# artProject_X.net
KiCad netlist of a schematic drawn in EAGLE
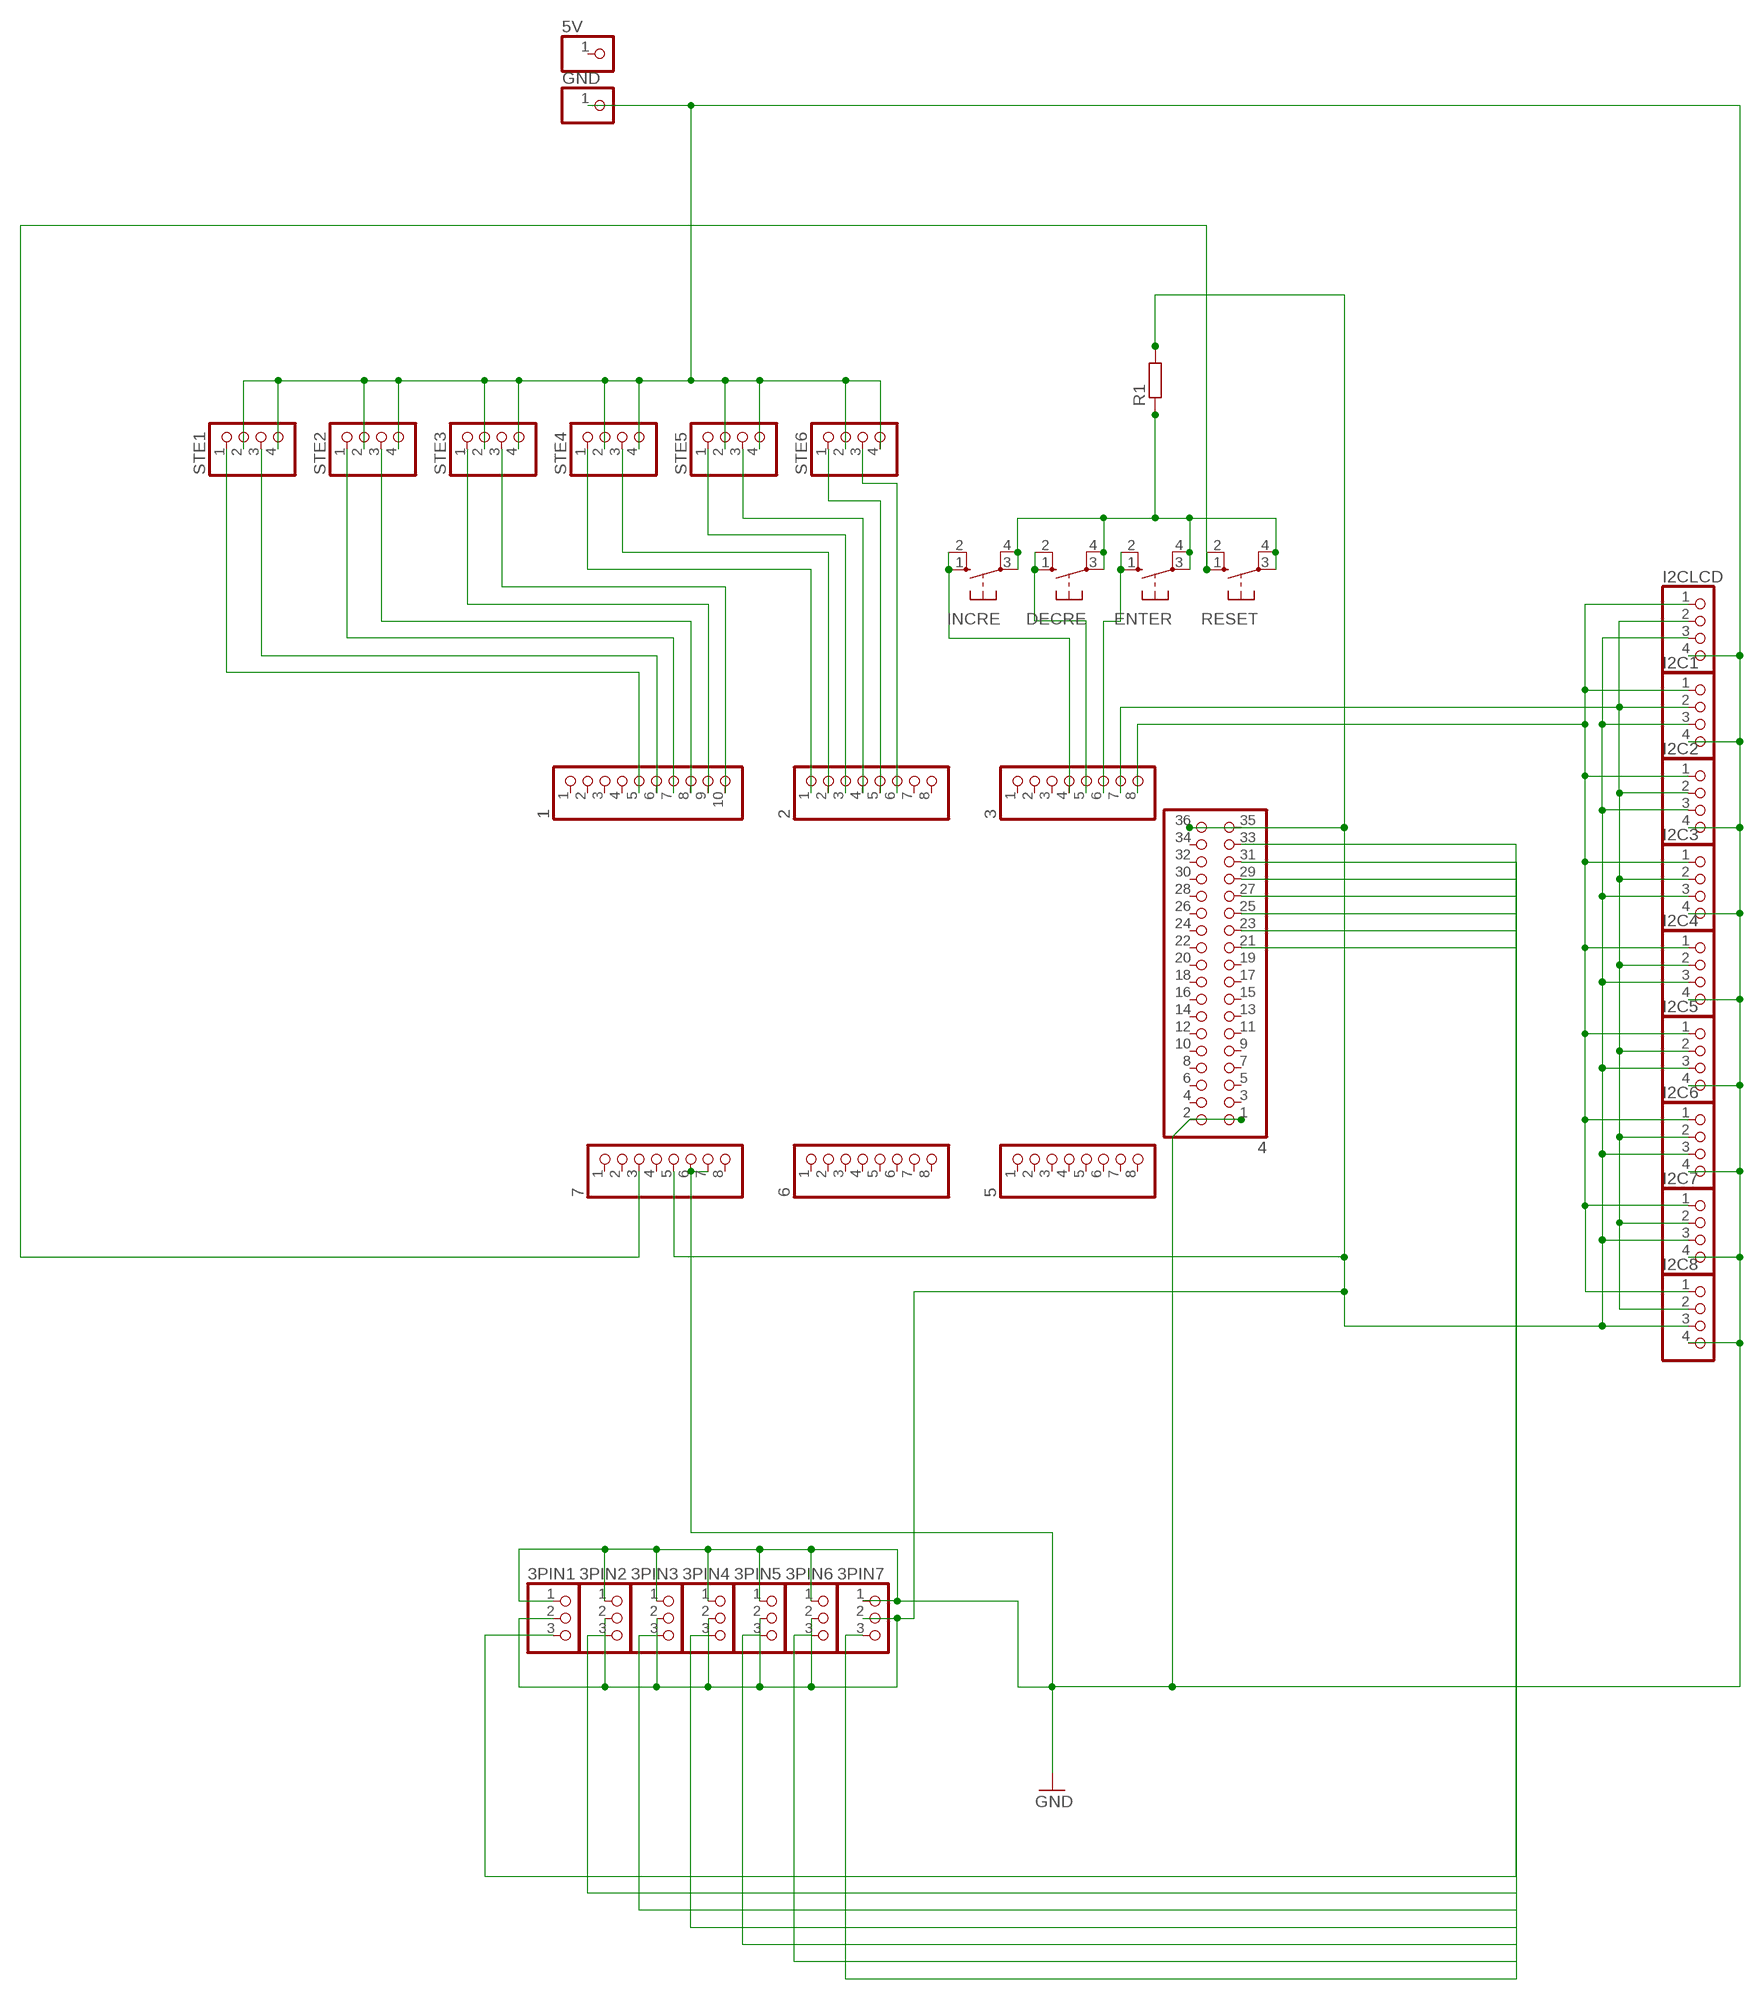
[diagram p0: schematic, sheet 1]

(export (version "E")
  (design (tool "Eeschema 10.0.6"))
  (components
    (comp (ref "1")
      (value "PINHD-1X10")
      (footprint "eagle-import:1X10")
      (libsource (lib "eagle-import") (part "PINHD-1X10"))
    )
    (comp (ref "2")
      (value "PINHD-1X8")
      (footprint "eagle-import:1X08")
      (libsource (lib "eagle-import") (part "PINHD-1X8"))
    )
    (comp (ref "3")
      (value "PINHD-1X8")
      (footprint "eagle-import:1X08")
      (libsource (lib "eagle-import") (part "PINHD-1X8"))
    )
    (comp (ref "3PIN1")
      (value "PINHD-1X3")
      (footprint "eagle-import:1X03")
      (libsource (lib "eagle-import") (part "PINHD-1X3"))
    )
    (comp (ref "3PIN2")
      (value "PINHD-1X3")
      (footprint "eagle-import:1X03")
      (libsource (lib "eagle-import") (part "PINHD-1X3"))
    )
    (comp (ref "3PIN3")
      (value "PINHD-1X3")
      (footprint "eagle-import:1X03")
      (libsource (lib "eagle-import") (part "PINHD-1X3"))
    )
    (comp (ref "3PIN4")
      (value "PINHD-1X3")
      (footprint "eagle-import:1X03")
      (libsource (lib "eagle-import") (part "PINHD-1X3"))
    )
    (comp (ref "3PIN5")
      (value "PINHD-1X3")
      (footprint "eagle-import:1X03")
      (libsource (lib "eagle-import") (part "PINHD-1X3"))
    )
    (comp (ref "3PIN6")
      (value "PINHD-1X3")
      (footprint "eagle-import:1X03")
      (libsource (lib "eagle-import") (part "PINHD-1X3"))
    )
    (comp (ref "3PIN7")
      (value "PINHD-1X3")
      (footprint "eagle-import:1X03")
      (libsource (lib "eagle-import") (part "PINHD-1X3"))
    )
    (comp (ref "4")
      (value "PINHD-2X18")
      (footprint "eagle-import:2X18")
      (libsource (lib "eagle-import") (part "PINHD-2X18"))
    )
    (comp (ref "5")
      (value "PINHD-1X8")
      (footprint "eagle-import:1X08")
      (libsource (lib "eagle-import") (part "PINHD-1X8"))
    )
    (comp (ref "5V")
      (value "PINHD-1X1")
      (footprint "eagle-import:1X01")
      (libsource (lib "eagle-import") (part "PINHD-1X1"))
    )
    (comp (ref "6")
      (value "PINHD-1X8")
      (footprint "eagle-import:1X08")
      (libsource (lib "eagle-import") (part "PINHD-1X8"))
    )
    (comp (ref "7")
      (value "PINHD-1X8")
      (footprint "eagle-import:1X08")
      (libsource (lib "eagle-import") (part "PINHD-1X8"))
    )
    (comp (ref "DECRE")
      (value "10-XX")
      (footprint "eagle-import:B3F-10XX")
      (fields (field (name "MPN") "B3F-1000"))
      (libsource (lib "eagle-import") (part "10-XX"))
    )
    (comp (ref "ENTER")
      (value "10-XX")
      (footprint "eagle-import:B3F-10XX")
      (fields (field (name "MPN") "B3F-1000"))
      (libsource (lib "eagle-import") (part "10-XX"))
    )
    (comp (ref "GND")
      (value "PINHD-1X1")
      (footprint "eagle-import:1X01")
      (libsource (lib "eagle-import") (part "PINHD-1X1"))
    )
    (comp (ref "I2C1")
      (value "PINHD-1X4")
      (footprint "eagle-import:1X04")
      (libsource (lib "eagle-import") (part "PINHD-1X4"))
    )
    (comp (ref "I2C2")
      (value "PINHD-1X4")
      (footprint "eagle-import:1X04")
      (libsource (lib "eagle-import") (part "PINHD-1X4"))
    )
    (comp (ref "I2C3")
      (value "PINHD-1X4")
      (footprint "eagle-import:1X04")
      (libsource (lib "eagle-import") (part "PINHD-1X4"))
    )
    (comp (ref "I2C4")
      (value "PINHD-1X4")
      (footprint "eagle-import:1X04")
      (libsource (lib "eagle-import") (part "PINHD-1X4"))
    )
    (comp (ref "I2C5")
      (value "PINHD-1X4")
      (footprint "eagle-import:1X04")
      (libsource (lib "eagle-import") (part "PINHD-1X4"))
    )
    (comp (ref "I2C6")
      (value "PINHD-1X4")
      (footprint "eagle-import:1X04")
      (libsource (lib "eagle-import") (part "PINHD-1X4"))
    )
    (comp (ref "I2C7")
      (value "PINHD-1X4")
      (footprint "eagle-import:1X04")
      (libsource (lib "eagle-import") (part "PINHD-1X4"))
    )
    (comp (ref "I2C8")
      (value "PINHD-1X4")
      (footprint "eagle-import:1X04")
      (libsource (lib "eagle-import") (part "PINHD-1X4"))
    )
    (comp (ref "I2CLCD")
      (value "PINHD-1X4")
      (footprint "eagle-import:1X04")
      (libsource (lib "eagle-import") (part "PINHD-1X4"))
    )
    (comp (ref "INCRE")
      (value "10-XX")
      (footprint "eagle-import:B3F-10XX")
      (fields (field (name "MPN") "B3F-1000"))
      (libsource (lib "eagle-import") (part "10-XX"))
    )
    (comp (ref "R1")
      (value "R-EU_0204/7")
      (footprint "eagle-import:0204_7")
      (libsource (lib "eagle-import") (part "R-EU_0204/7"))
    )
    (comp (ref "RESET")
      (value "10-XX")
      (footprint "eagle-import:B3F-10XX")
      (fields (field (name "MPN") "B3F-1000"))
      (libsource (lib "eagle-import") (part "10-XX"))
    )
    (comp (ref "STE1")
      (value "PINHD-1X4")
      (footprint "eagle-import:1X04")
      (libsource (lib "eagle-import") (part "PINHD-1X4"))
    )
    (comp (ref "STE2")
      (value "PINHD-1X4")
      (footprint "eagle-import:1X04")
      (libsource (lib "eagle-import") (part "PINHD-1X4"))
    )
    (comp (ref "STE3")
      (value "PINHD-1X4")
      (footprint "eagle-import:1X04")
      (libsource (lib "eagle-import") (part "PINHD-1X4"))
    )
    (comp (ref "STE4")
      (value "PINHD-1X4")
      (footprint "eagle-import:1X04")
      (libsource (lib "eagle-import") (part "PINHD-1X4"))
    )
    (comp (ref "STE5")
      (value "PINHD-1X4")
      (footprint "eagle-import:1X04")
      (libsource (lib "eagle-import") (part "PINHD-1X4"))
    )
    (comp (ref "STE6")
      (value "PINHD-1X4")
      (footprint "eagle-import:1X04")
      (libsource (lib "eagle-import") (part "PINHD-1X4"))
    )
  )
  (nets
    (net (code "1") (name "GND") (class "Default")
      (node (ref "3PIN1") (pin "1") (pinfunction "1_1") (pintype "passive"))
      (node (ref "3PIN2") (pin "1") (pinfunction "1_1") (pintype "passive"))
      (node (ref "3PIN3") (pin "1") (pinfunction "1_1") (pintype "passive"))
      (node (ref "3PIN4") (pin "1") (pinfunction "1_1") (pintype "passive"))
      (node (ref "3PIN5") (pin "1") (pinfunction "1_1") (pintype "passive"))
      (node (ref "3PIN6") (pin "1") (pinfunction "1_1") (pintype "passive"))
      (node (ref "3PIN7") (pin "1") (pinfunction "1_1") (pintype "passive"))
      (node (ref "4") (pin "1") (pinfunction "1_1") (pintype "passive"))
      (node (ref "4") (pin "2") (pinfunction "2_2") (pintype "passive"))
      (node (ref "7") (pin "6") (pinfunction "6_6") (pintype "passive"))
      (node (ref "7") (pin "7") (pinfunction "7_7") (pintype "passive"))
      (node (ref "GND") (pin "1") (pinfunction "1_1") (pintype "passive"))
      (node (ref "I2C1") (pin "4") (pinfunction "4_4") (pintype "passive"))
      (node (ref "I2C2") (pin "4") (pinfunction "4_4") (pintype "passive"))
      (node (ref "I2C3") (pin "4") (pinfunction "4_4") (pintype "passive"))
      (node (ref "I2C4") (pin "4") (pinfunction "4_4") (pintype "passive"))
      (node (ref "I2C5") (pin "4") (pinfunction "4_4") (pintype "passive"))
      (node (ref "I2C6") (pin "4") (pinfunction "4_4") (pintype "passive"))
      (node (ref "I2C7") (pin "4") (pinfunction "4_4") (pintype "passive"))
      (node (ref "I2C8") (pin "4") (pinfunction "4_4") (pintype "passive"))
      (node (ref "I2CLCD") (pin "4") (pinfunction "4_4") (pintype "passive"))
      (node (ref "STE1") (pin "2") (pinfunction "2_2") (pintype "passive"))
      (node (ref "STE1") (pin "4") (pinfunction "4_4") (pintype "passive"))
      (node (ref "STE2") (pin "2") (pinfunction "2_2") (pintype "passive"))
      (node (ref "STE2") (pin "4") (pinfunction "4_4") (pintype "passive"))
      (node (ref "STE3") (pin "2") (pinfunction "2_2") (pintype "passive"))
      (node (ref "STE3") (pin "4") (pinfunction "4_4") (pintype "passive"))
      (node (ref "STE4") (pin "2") (pinfunction "2_2") (pintype "passive"))
      (node (ref "STE4") (pin "4") (pinfunction "4_4") (pintype "passive"))
      (node (ref "STE5") (pin "2") (pinfunction "2_2") (pintype "passive"))
      (node (ref "STE5") (pin "4") (pinfunction "4_4") (pintype "passive"))
      (node (ref "STE6") (pin "2") (pinfunction "2_2") (pintype "passive"))
      (node (ref "STE6") (pin "4") (pinfunction "4_4") (pintype "passive"))
    )
    (net (code "2") (name "Net-(1-Pad5)") (class "Default")
      (node (ref "1") (pin "5") (pinfunction "5_5") (pintype "passive"))
      (node (ref "STE1") (pin "1") (pinfunction "1_1") (pintype "passive"))
    )
    (net (code "3") (name "Net-(1-Pad6)") (class "Default")
      (node (ref "1") (pin "6") (pinfunction "6_6") (pintype "passive"))
      (node (ref "STE1") (pin "3") (pinfunction "3_3") (pintype "passive"))
    )
    (net (code "4") (name "Net-(1-Pad7)") (class "Default")
      (node (ref "1") (pin "7") (pinfunction "7_7") (pintype "passive"))
      (node (ref "STE2") (pin "1") (pinfunction "1_1") (pintype "passive"))
    )
    (net (code "5") (name "Net-(1-Pad8)") (class "Default")
      (node (ref "1") (pin "8") (pinfunction "8_8") (pintype "passive"))
      (node (ref "STE2") (pin "3") (pinfunction "3_3") (pintype "passive"))
    )
    (net (code "6") (name "Net-(1-Pad9)") (class "Default")
      (node (ref "1") (pin "9") (pinfunction "9_9") (pintype "passive"))
      (node (ref "STE3") (pin "1") (pinfunction "1_1") (pintype "passive"))
    )
    (net (code "7") (name "Net-(1-Pad10)") (class "Default")
      (node (ref "1") (pin "10") (pinfunction "10_10") (pintype "passive"))
      (node (ref "STE3") (pin "3") (pinfunction "3_3") (pintype "passive"))
    )
    (net (code "8") (name "Net-(2-Pad1)") (class "Default")
      (node (ref "2") (pin "1") (pinfunction "1_1") (pintype "passive"))
      (node (ref "STE4") (pin "1") (pinfunction "1_1") (pintype "passive"))
    )
    (net (code "9") (name "Net-(2-Pad2)") (class "Default")
      (node (ref "2") (pin "2") (pinfunction "2_2") (pintype "passive"))
      (node (ref "STE4") (pin "3") (pinfunction "3_3") (pintype "passive"))
    )
    (net (code "10") (name "Net-(2-Pad3)") (class "Default")
      (node (ref "2") (pin "3") (pinfunction "3_3") (pintype "passive"))
      (node (ref "STE5") (pin "1") (pinfunction "1_1") (pintype "passive"))
    )
    (net (code "11") (name "Net-(2-Pad4)") (class "Default")
      (node (ref "2") (pin "4") (pinfunction "4_4") (pintype "passive"))
      (node (ref "STE5") (pin "3") (pinfunction "3_3") (pintype "passive"))
    )
    (net (code "12") (name "Net-(2-Pad5)") (class "Default")
      (node (ref "2") (pin "5") (pinfunction "5_5") (pintype "passive"))
      (node (ref "STE6") (pin "1") (pinfunction "1_1") (pintype "passive"))
    )
    (net (code "13") (name "Net-(2-Pad6)") (class "Default")
      (node (ref "2") (pin "6") (pinfunction "6_6") (pintype "passive"))
      (node (ref "STE6") (pin "3") (pinfunction "3_3") (pintype "passive"))
    )
    (net (code "14") (name "Net-(3-Pad7)") (class "Default")
      (node (ref "3") (pin "7") (pinfunction "7_7") (pintype "passive"))
      (node (ref "I2C1") (pin "2") (pinfunction "2_2") (pintype "passive"))
      (node (ref "I2C2") (pin "2") (pinfunction "2_2") (pintype "passive"))
      (node (ref "I2C3") (pin "2") (pinfunction "2_2") (pintype "passive"))
      (node (ref "I2C4") (pin "2") (pinfunction "2_2") (pintype "passive"))
      (node (ref "I2C5") (pin "2") (pinfunction "2_2") (pintype "passive"))
      (node (ref "I2C6") (pin "2") (pinfunction "2_2") (pintype "passive"))
      (node (ref "I2C7") (pin "2") (pinfunction "2_2") (pintype "passive"))
      (node (ref "I2C8") (pin "2") (pinfunction "2_2") (pintype "passive"))
      (node (ref "I2CLCD") (pin "2") (pinfunction "2_2") (pintype "passive"))
    )
    (net (code "15") (name "Net-(3-Pad8)") (class "Default")
      (node (ref "3") (pin "8") (pinfunction "8_8") (pintype "passive"))
      (node (ref "I2C1") (pin "1") (pinfunction "1_1") (pintype "passive"))
      (node (ref "I2C2") (pin "1") (pinfunction "1_1") (pintype "passive"))
      (node (ref "I2C3") (pin "1") (pinfunction "1_1") (pintype "passive"))
      (node (ref "I2C4") (pin "1") (pinfunction "1_1") (pintype "passive"))
      (node (ref "I2C5") (pin "1") (pinfunction "1_1") (pintype "passive"))
      (node (ref "I2C6") (pin "1") (pinfunction "1_1") (pintype "passive"))
      (node (ref "I2C7") (pin "1") (pinfunction "1_1") (pintype "passive"))
      (node (ref "I2C8") (pin "1") (pinfunction "1_1") (pintype "passive"))
      (node (ref "I2CLCD") (pin "1") (pinfunction "1_1") (pintype "passive"))
    )
    (net (code "16") (name "Net-(3PIN1-Pad2)") (class "Default")
      (node (ref "3PIN1") (pin "2") (pinfunction "2_2") (pintype "passive"))
      (node (ref "3PIN2") (pin "2") (pinfunction "2_2") (pintype "passive"))
      (node (ref "3PIN3") (pin "2") (pinfunction "2_2") (pintype "passive"))
      (node (ref "3PIN4") (pin "2") (pinfunction "2_2") (pintype "passive"))
      (node (ref "3PIN5") (pin "2") (pinfunction "2_2") (pintype "passive"))
      (node (ref "3PIN6") (pin "2") (pinfunction "2_2") (pintype "passive"))
      (node (ref "3PIN7") (pin "2") (pinfunction "2_2") (pintype "passive"))
      (node (ref "4") (pin "35") (pinfunction "35_35") (pintype "passive"))
      (node (ref "4") (pin "36") (pinfunction "36_36") (pintype "passive"))
      (node (ref "7") (pin "5") (pinfunction "5_5") (pintype "passive"))
      (node (ref "I2C1") (pin "3") (pinfunction "3_3") (pintype "passive"))
      (node (ref "I2C2") (pin "3") (pinfunction "3_3") (pintype "passive"))
      (node (ref "I2C3") (pin "3") (pinfunction "3_3") (pintype "passive"))
      (node (ref "I2C4") (pin "3") (pinfunction "3_3") (pintype "passive"))
      (node (ref "I2C5") (pin "3") (pinfunction "3_3") (pintype "passive"))
      (node (ref "I2C6") (pin "3") (pinfunction "3_3") (pintype "passive"))
      (node (ref "I2C7") (pin "3") (pinfunction "3_3") (pintype "passive"))
      (node (ref "I2C8") (pin "3") (pinfunction "3_3") (pintype "passive"))
      (node (ref "I2CLCD") (pin "3") (pinfunction "3_3") (pintype "passive"))
      (node (ref "R1") (pin "2") (pinfunction "2_2") (pintype "passive"))
    )
    (net (code "17") (name "Net-(3PIN1-Pad3)") (class "Default")
      (node (ref "3PIN1") (pin "3") (pinfunction "3_3") (pintype "passive"))
      (node (ref "4") (pin "33") (pinfunction "33_33") (pintype "passive"))
    )
    (net (code "18") (name "Net-(3PIN2-Pad3)") (class "Default")
      (node (ref "3PIN2") (pin "3") (pinfunction "3_3") (pintype "passive"))
      (node (ref "4") (pin "31") (pinfunction "31_31") (pintype "passive"))
    )
    (net (code "19") (name "Net-(3PIN3-Pad3)") (class "Default")
      (node (ref "3PIN3") (pin "3") (pinfunction "3_3") (pintype "passive"))
      (node (ref "4") (pin "29") (pinfunction "29_29") (pintype "passive"))
    )
    (net (code "20") (name "Net-(3PIN4-Pad3)") (class "Default")
      (node (ref "3PIN4") (pin "3") (pinfunction "3_3") (pintype "passive"))
      (node (ref "4") (pin "27") (pinfunction "27_27") (pintype "passive"))
    )
    (net (code "21") (name "Net-(3PIN5-Pad3)") (class "Default")
      (node (ref "3PIN5") (pin "3") (pinfunction "3_3") (pintype "passive"))
      (node (ref "4") (pin "25") (pinfunction "25_25") (pintype "passive"))
    )
    (net (code "22") (name "Net-(3PIN6-Pad3)") (class "Default")
      (node (ref "3PIN6") (pin "3") (pinfunction "3_3") (pintype "passive"))
      (node (ref "4") (pin "23") (pinfunction "23_23") (pintype "passive"))
    )
    (net (code "23") (name "Net-(3PIN7-Pad3)") (class "Default")
      (node (ref "3PIN7") (pin "3") (pinfunction "3_3") (pintype "passive"))
      (node (ref "4") (pin "21") (pinfunction "21_21") (pintype "passive"))
    )
    (net (code "24") (name "Net-(DECRE-P)") (class "Default")
      (node (ref "DECRE") (pin "3") (pinfunction "P_3") (pintype "passive"))
      (node (ref "DECRE") (pin "4") (pinfunction "P1_4") (pintype "passive"))
      (node (ref "ENTER") (pin "3") (pinfunction "P_3") (pintype "passive"))
      (node (ref "ENTER") (pin "4") (pinfunction "P1_4") (pintype "passive"))
      (node (ref "INCRE") (pin "3") (pinfunction "P_3") (pintype "passive"))
      (node (ref "INCRE") (pin "4") (pinfunction "P1_4") (pintype "passive"))
      (node (ref "R1") (pin "1") (pinfunction "1_1") (pintype "passive"))
      (node (ref "RESET") (pin "3") (pinfunction "P_3") (pintype "passive"))
      (node (ref "RESET") (pin "4") (pinfunction "P1_4") (pintype "passive"))
    )
    (net (code "25") (name "Net-(DECRE-S)") (class "Default")
      (node (ref "3") (pin "5") (pinfunction "5_5") (pintype "passive"))
      (node (ref "DECRE") (pin "1") (pinfunction "S_1") (pintype "passive"))
      (node (ref "DECRE") (pin "2") (pinfunction "S1_2") (pintype "passive"))
    )
    (net (code "26") (name "Net-(ENTER-S)") (class "Default")
      (node (ref "3") (pin "6") (pinfunction "6_6") (pintype "passive"))
      (node (ref "ENTER") (pin "1") (pinfunction "S_1") (pintype "passive"))
      (node (ref "ENTER") (pin "2") (pinfunction "S1_2") (pintype "passive"))
    )
    (net (code "27") (name "Net-(INCRE-S)") (class "Default")
      (node (ref "3") (pin "4") (pinfunction "4_4") (pintype "passive"))
      (node (ref "INCRE") (pin "1") (pinfunction "S_1") (pintype "passive"))
      (node (ref "INCRE") (pin "2") (pinfunction "S1_2") (pintype "passive"))
    )
    (net (code "28") (name "Net-(RESET-S)") (class "Default")
      (node (ref "7") (pin "3") (pinfunction "3_3") (pintype "passive"))
      (node (ref "RESET") (pin "1") (pinfunction "S_1") (pintype "passive"))
      (node (ref "RESET") (pin "2") (pinfunction "S1_2") (pintype "passive"))
    )
    (net (code "29") (name "unconnected-(1-Pad1)") (class "Default")
      (node (ref "1") (pin "1") (pinfunction "1_1") (pintype "passive"))
    )
    (net (code "30") (name "unconnected-(1-Pad2)") (class "Default")
      (node (ref "1") (pin "2") (pinfunction "2_2") (pintype "passive"))
    )
    (net (code "31") (name "unconnected-(1-Pad3)") (class "Default")
      (node (ref "1") (pin "3") (pinfunction "3_3") (pintype "passive"))
    )
    (net (code "32") (name "unconnected-(1-Pad4)") (class "Default")
      (node (ref "1") (pin "4") (pinfunction "4_4") (pintype "passive"))
    )
    (net (code "33") (name "unconnected-(2-Pad7)") (class "Default")
      (node (ref "2") (pin "7") (pinfunction "7_7") (pintype "passive"))
    )
    (net (code "34") (name "unconnected-(2-Pad8)") (class "Default")
      (node (ref "2") (pin "8") (pinfunction "8_8") (pintype "passive"))
    )
    (net (code "35") (name "unconnected-(3-Pad1)") (class "Default")
      (node (ref "3") (pin "1") (pinfunction "1_1") (pintype "passive"))
    )
    (net (code "36") (name "unconnected-(3-Pad2)") (class "Default")
      (node (ref "3") (pin "2") (pinfunction "2_2") (pintype "passive"))
    )
    (net (code "37") (name "unconnected-(3-Pad3)") (class "Default")
      (node (ref "3") (pin "3") (pinfunction "3_3") (pintype "passive"))
    )
    (net (code "38") (name "unconnected-(4-Pad3)") (class "Default")
      (node (ref "4") (pin "3") (pinfunction "3_3") (pintype "passive"))
    )
    (net (code "39") (name "unconnected-(4-Pad4)") (class "Default")
      (node (ref "4") (pin "4") (pinfunction "4_4") (pintype "passive"))
    )
    (net (code "40") (name "unconnected-(4-Pad5)") (class "Default")
      (node (ref "4") (pin "5") (pinfunction "5_5") (pintype "passive"))
    )
    (net (code "41") (name "unconnected-(4-Pad6)") (class "Default")
      (node (ref "4") (pin "6") (pinfunction "6_6") (pintype "passive"))
    )
    (net (code "42") (name "unconnected-(4-Pad7)") (class "Default")
      (node (ref "4") (pin "7") (pinfunction "7_7") (pintype "passive"))
    )
    (net (code "43") (name "unconnected-(4-Pad8)") (class "Default")
      (node (ref "4") (pin "8") (pinfunction "8_8") (pintype "passive"))
    )
    (net (code "44") (name "unconnected-(4-Pad9)") (class "Default")
      (node (ref "4") (pin "9") (pinfunction "9_9") (pintype "passive"))
    )
    (net (code "45") (name "unconnected-(4-Pad10)") (class "Default")
      (node (ref "4") (pin "10") (pinfunction "10_10") (pintype "passive"))
    )
    (net (code "46") (name "unconnected-(4-Pad11)") (class "Default")
      (node (ref "4") (pin "11") (pinfunction "11_11") (pintype "passive"))
    )
    (net (code "47") (name "unconnected-(4-Pad12)") (class "Default")
      (node (ref "4") (pin "12") (pinfunction "12_12") (pintype "passive"))
    )
    (net (code "48") (name "unconnected-(4-Pad13)") (class "Default")
      (node (ref "4") (pin "13") (pinfunction "13_13") (pintype "passive"))
    )
    (net (code "49") (name "unconnected-(4-Pad14)") (class "Default")
      (node (ref "4") (pin "14") (pinfunction "14_14") (pintype "passive"))
    )
    (net (code "50") (name "unconnected-(4-Pad15)") (class "Default")
      (node (ref "4") (pin "15") (pinfunction "15_15") (pintype "passive"))
    )
    (net (code "51") (name "unconnected-(4-Pad16)") (class "Default")
      (node (ref "4") (pin "16") (pinfunction "16_16") (pintype "passive"))
    )
    (net (code "52") (name "unconnected-(4-Pad17)") (class "Default")
      (node (ref "4") (pin "17") (pinfunction "17_17") (pintype "passive"))
    )
    (net (code "53") (name "unconnected-(4-Pad18)") (class "Default")
      (node (ref "4") (pin "18") (pinfunction "18_18") (pintype "passive"))
    )
    (net (code "54") (name "unconnected-(4-Pad19)") (class "Default")
      (node (ref "4") (pin "19") (pinfunction "19_19") (pintype "passive"))
    )
    (net (code "55") (name "unconnected-(4-Pad20)") (class "Default")
      (node (ref "4") (pin "20") (pinfunction "20_20") (pintype "passive"))
    )
    (net (code "56") (name "unconnected-(4-Pad22)") (class "Default")
      (node (ref "4") (pin "22") (pinfunction "22_22") (pintype "passive"))
    )
    (net (code "57") (name "unconnected-(4-Pad24)") (class "Default")
      (node (ref "4") (pin "24") (pinfunction "24_24") (pintype "passive"))
    )
    (net (code "58") (name "unconnected-(4-Pad26)") (class "Default")
      (node (ref "4") (pin "26") (pinfunction "26_26") (pintype "passive"))
    )
    (net (code "59") (name "unconnected-(4-Pad28)") (class "Default")
      (node (ref "4") (pin "28") (pinfunction "28_28") (pintype "passive"))
    )
    (net (code "60") (name "unconnected-(4-Pad30)") (class "Default")
      (node (ref "4") (pin "30") (pinfunction "30_30") (pintype "passive"))
    )
    (net (code "61") (name "unconnected-(4-Pad32)") (class "Default")
      (node (ref "4") (pin "32") (pinfunction "32_32") (pintype "passive"))
    )
    (net (code "62") (name "unconnected-(4-Pad34)") (class "Default")
      (node (ref "4") (pin "34") (pinfunction "34_34") (pintype "passive"))
    )
    (net (code "63") (name "unconnected-(5-Pad1)") (class "Default")
      (node (ref "5") (pin "1") (pinfunction "1_1") (pintype "passive"))
    )
    (net (code "64") (name "unconnected-(5-Pad2)") (class "Default")
      (node (ref "5") (pin "2") (pinfunction "2_2") (pintype "passive"))
    )
    (net (code "65") (name "unconnected-(5-Pad3)") (class "Default")
      (node (ref "5") (pin "3") (pinfunction "3_3") (pintype "passive"))
    )
    (net (code "66") (name "unconnected-(5-Pad4)") (class "Default")
      (node (ref "5") (pin "4") (pinfunction "4_4") (pintype "passive"))
    )
    (net (code "67") (name "unconnected-(5-Pad5)") (class "Default")
      (node (ref "5") (pin "5") (pinfunction "5_5") (pintype "passive"))
    )
    (net (code "68") (name "unconnected-(5-Pad6)") (class "Default")
      (node (ref "5") (pin "6") (pinfunction "6_6") (pintype "passive"))
    )
    (net (code "69") (name "unconnected-(5-Pad7)") (class "Default")
      (node (ref "5") (pin "7") (pinfunction "7_7") (pintype "passive"))
    )
    (net (code "70") (name "unconnected-(5-Pad8)") (class "Default")
      (node (ref "5") (pin "8") (pinfunction "8_8") (pintype "passive"))
    )
    (net (code "71") (name "unconnected-(5V-Pad1)") (class "Default")
      (node (ref "5V") (pin "1") (pinfunction "1_1") (pintype "passive"))
    )
    (net (code "72") (name "unconnected-(6-Pad1)") (class "Default")
      (node (ref "6") (pin "1") (pinfunction "1_1") (pintype "passive"))
    )
    (net (code "73") (name "unconnected-(6-Pad2)") (class "Default")
      (node (ref "6") (pin "2") (pinfunction "2_2") (pintype "passive"))
    )
    (net (code "74") (name "unconnected-(6-Pad3)") (class "Default")
      (node (ref "6") (pin "3") (pinfunction "3_3") (pintype "passive"))
    )
    (net (code "75") (name "unconnected-(6-Pad4)") (class "Default")
      (node (ref "6") (pin "4") (pinfunction "4_4") (pintype "passive"))
    )
    (net (code "76") (name "unconnected-(6-Pad5)") (class "Default")
      (node (ref "6") (pin "5") (pinfunction "5_5") (pintype "passive"))
    )
    (net (code "77") (name "unconnected-(6-Pad6)") (class "Default")
      (node (ref "6") (pin "6") (pinfunction "6_6") (pintype "passive"))
    )
    (net (code "78") (name "unconnected-(6-Pad7)") (class "Default")
      (node (ref "6") (pin "7") (pinfunction "7_7") (pintype "passive"))
    )
    (net (code "79") (name "unconnected-(6-Pad8)") (class "Default")
      (node (ref "6") (pin "8") (pinfunction "8_8") (pintype "passive"))
    )
    (net (code "80") (name "unconnected-(7-Pad1)") (class "Default")
      (node (ref "7") (pin "1") (pinfunction "1_1") (pintype "passive"))
    )
    (net (code "81") (name "unconnected-(7-Pad2)") (class "Default")
      (node (ref "7") (pin "2") (pinfunction "2_2") (pintype "passive"))
    )
    (net (code "82") (name "unconnected-(7-Pad4)") (class "Default")
      (node (ref "7") (pin "4") (pinfunction "4_4") (pintype "passive"))
    )
    (net (code "83") (name "unconnected-(7-Pad8)") (class "Default")
      (node (ref "7") (pin "8") (pinfunction "8_8") (pintype "passive"))
    )
  )
)
